# MCU025B_XDS110_MCU.net
KiCad netlist of a schematic drawn in Altium Designer
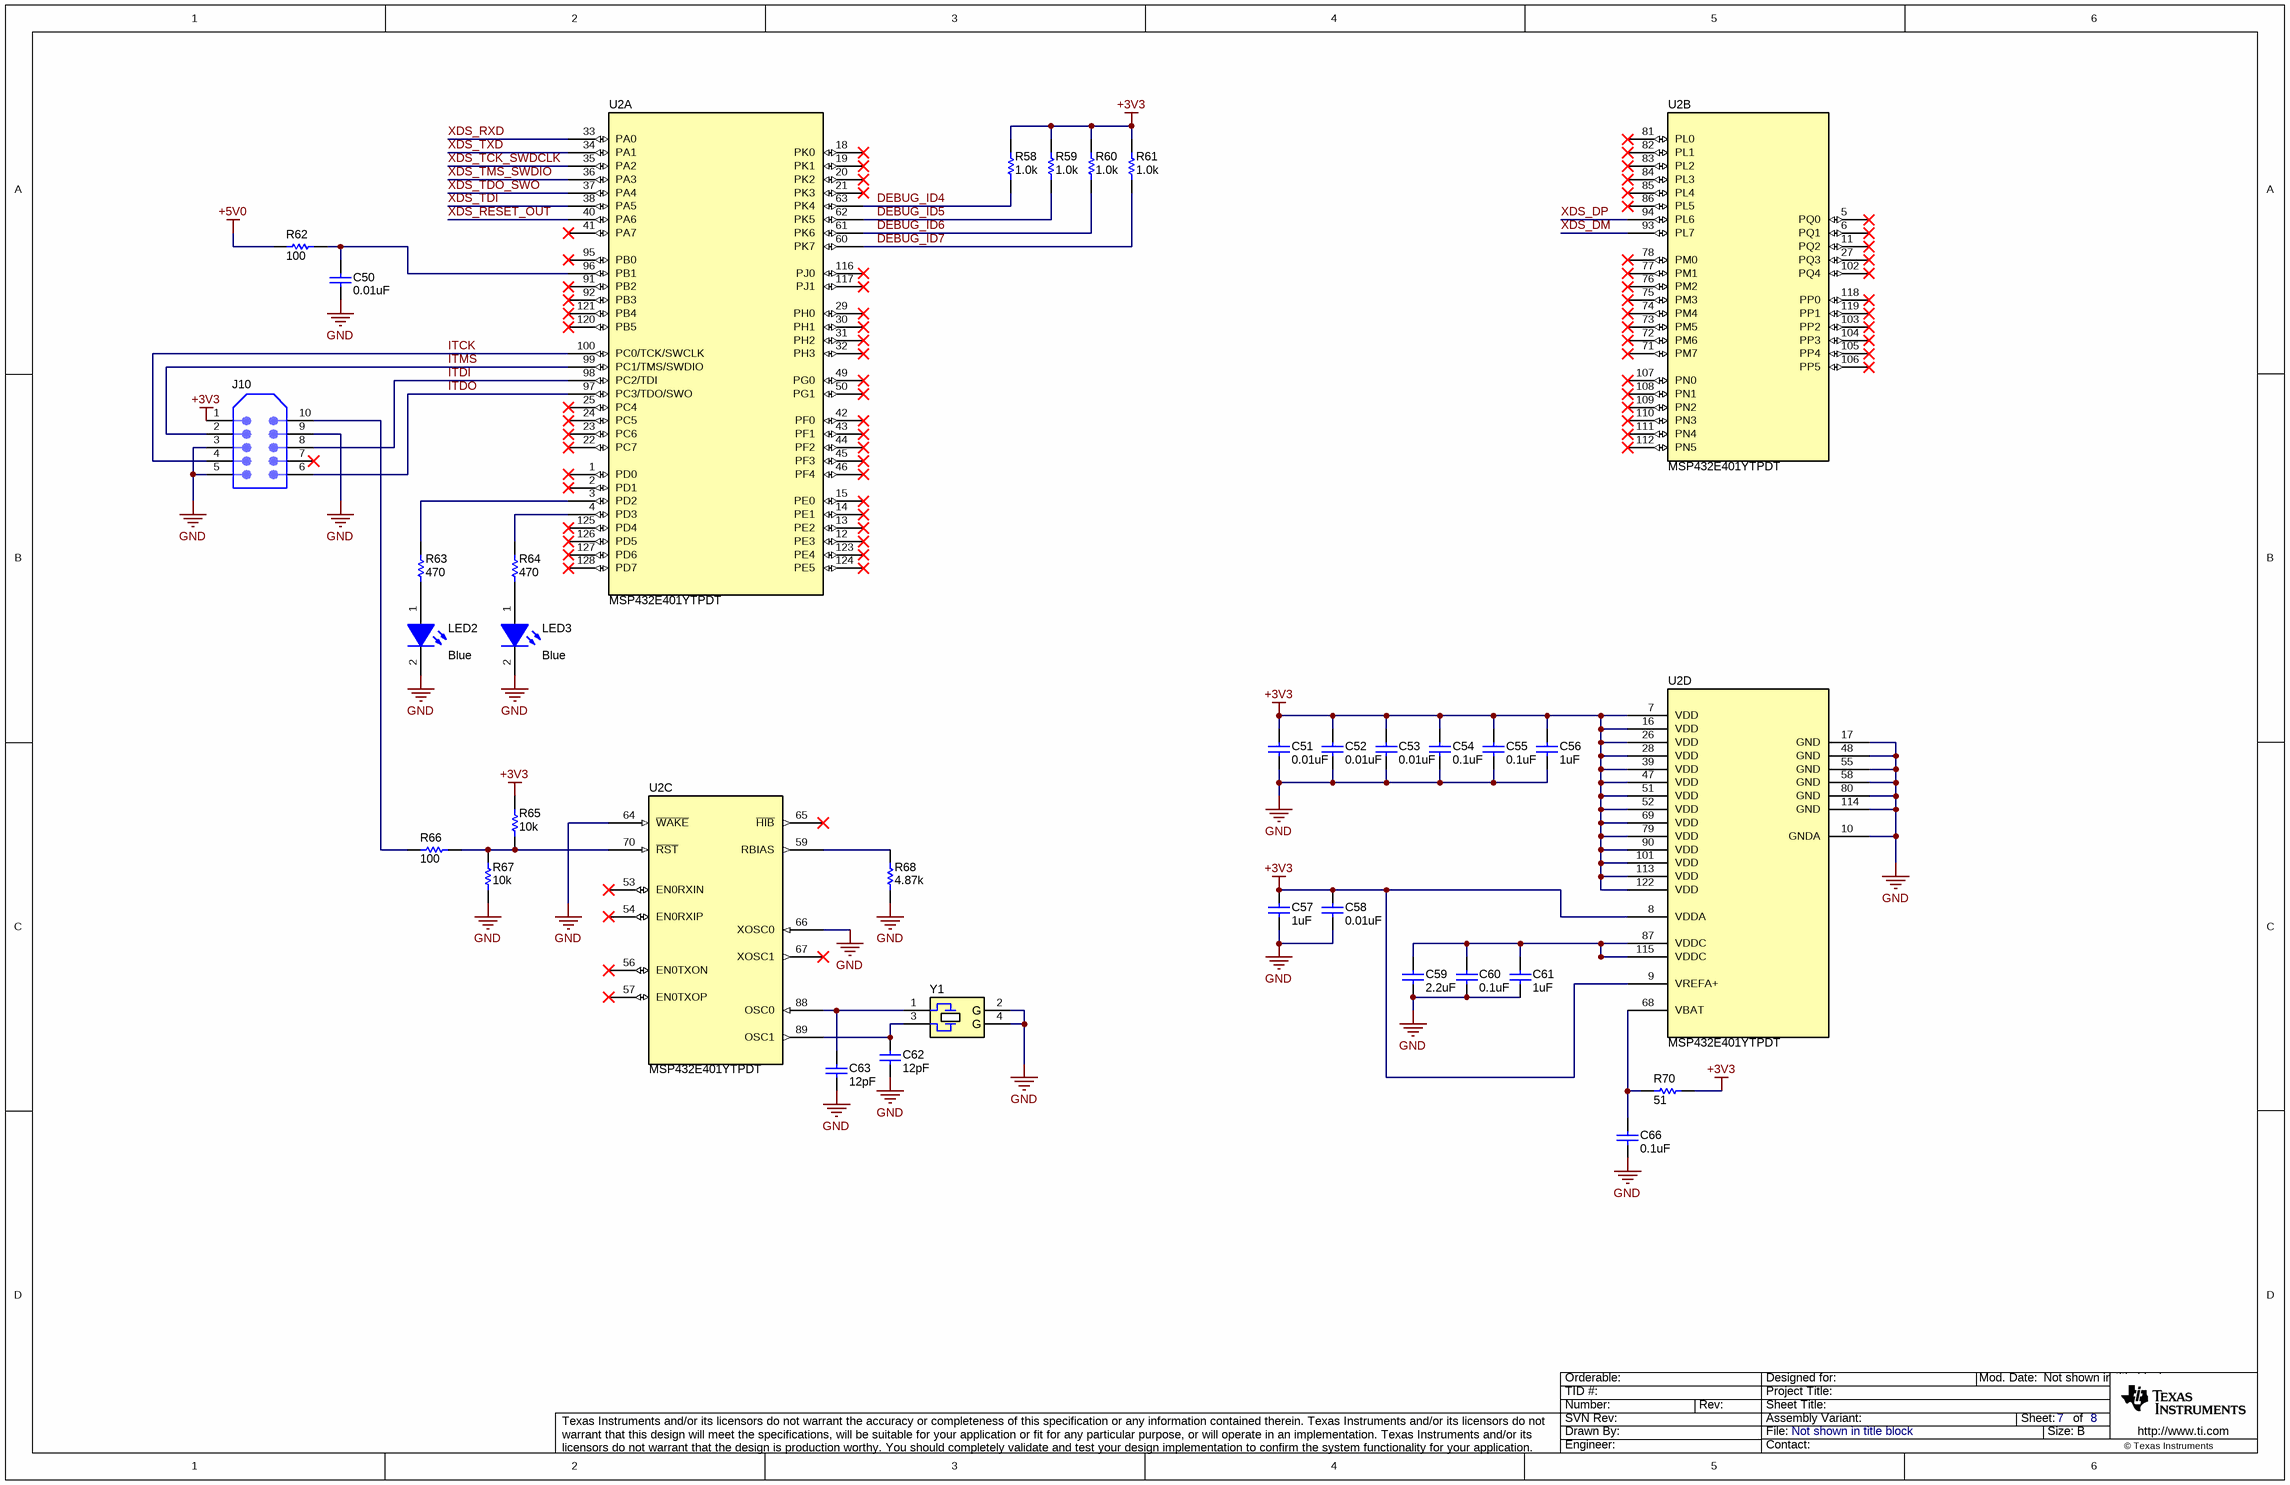
[diagram p0: MCU025B_XDS110_MCU.SchDoc]

(export (version "E")
  (design (tool "Eeschema 10.0.6"))
  (components
    (comp (ref "C50")
      (value "GRM155R71E103KA01D")
      (footprint "0402")
      (description "CAP, CERM, 0.01 uF, 25 V, +/- 10%, X7R, 0402")
      (fields
        (field (name "VALUEDISPLAYED") "0.01uF")
        (field (name "MANUFACTURER") "MuRata")
        (field (name "PUBLISHER") "Texas Instruments")
      )
      (libsource (lib "Altium Vault - TI") (part "Capacitor"))
    )
    (comp (ref "C51")
      (value "GRM155R71E103KA01D")
      (footprint "0402")
      (description "CAP, CERM, 0.01 uF, 25 V, +/- 10%, X7R, 0402")
      (fields
        (field (name "VALUEDISPLAYED") "0.01uF")
        (field (name "MANUFACTURER") "MuRata")
        (field (name "PUBLISHER") "Texas Instruments")
      )
      (libsource (lib "Altium Vault - TI") (part "Capacitor"))
    )
    (comp (ref "C52")
      (value "GRM155R71E103KA01D")
      (footprint "0402")
      (description "CAP, CERM, 0.01 uF, 25 V, +/- 10%, X7R, 0402")
      (fields
        (field (name "VALUEDISPLAYED") "0.01uF")
        (field (name "MANUFACTURER") "MuRata")
        (field (name "PUBLISHER") "Texas Instruments")
      )
      (libsource (lib "Altium Vault - TI") (part "Capacitor"))
    )
    (comp (ref "C53")
      (value "GRM155R71E103KA01D")
      (footprint "0402")
      (description "CAP, CERM, 0.01 uF, 25 V, +/- 10%, X7R, 0402")
      (fields
        (field (name "VALUEDISPLAYED") "0.01uF")
        (field (name "MANUFACTURER") "MuRata")
        (field (name "PUBLISHER") "Texas Instruments")
      )
      (libsource (lib "Altium Vault - TI") (part "Capacitor"))
    )
    (comp (ref "C54")
      (value "GRM155R70J104KA01D")
      (footprint "0402")
      (description "CAP, CERM, 0.1 uF, 6.3 V, +/- 10%, X7R, 0402")
      (fields
        (field (name "VALUEDISPLAYED") "0.1uF")
        (field (name "MANUFACTURER") "MuRata")
        (field (name "PUBLISHER") "Texas Instruments")
      )
      (libsource (lib "Altium Vault - TI") (part "Capacitor"))
    )
    (comp (ref "C55")
      (value "GRM155R70J104KA01D")
      (footprint "0402")
      (description "CAP, CERM, 0.1 uF, 6.3 V, +/- 10%, X7R, 0402")
      (fields
        (field (name "VALUEDISPLAYED") "0.1uF")
        (field (name "MANUFACTURER") "MuRata")
        (field (name "PUBLISHER") "Texas Instruments")
      )
      (libsource (lib "Altium Vault - TI") (part "Capacitor"))
    )
    (comp (ref "C56")
      (value "GRM155R61A105KE15D")
      (footprint "0402")
      (description "CAP, CERM, 1 uF, 10 V, +/- 10%, X5R, 0402")
      (fields
        (field (name "VALUEDISPLAYED") "1uF")
        (field (name "MANUFACTURER") "MuRata")
        (field (name "PUBLISHER") "Texas Instruments")
      )
      (libsource (lib "Altium Vault - TI") (part "Capacitor"))
    )
    (comp (ref "C57")
      (value "GRM155R61A105KE15D")
      (footprint "0402")
      (description "CAP, CERM, 1 uF, 10 V, +/- 10%, X5R, 0402")
      (fields
        (field (name "VALUEDISPLAYED") "1uF")
        (field (name "MANUFACTURER") "MuRata")
        (field (name "PUBLISHER") "Texas Instruments")
      )
      (libsource (lib "Altium Vault - TI") (part "Capacitor"))
    )
    (comp (ref "C58")
      (value "GRM155R71E103KA01D")
      (footprint "0402")
      (description "CAP, CERM, 0.01 uF, 25 V, +/- 10%, X7R, 0402")
      (fields
        (field (name "VALUEDISPLAYED") "0.01uF")
        (field (name "MANUFACTURER") "MuRata")
        (field (name "PUBLISHER") "Texas Instruments")
      )
      (libsource (lib "Altium Vault - TI") (part "Capacitor"))
    )
    (comp (ref "C59")
      (value "GRM155R60J225KE95D")
      (footprint "0402")
      (description "CAP, CERM, 2.2 uF, 6.3 V, +/- 10%, X5R, 0402")
      (fields
        (field (name "VALUEDISPLAYED") "2.2uF")
        (field (name "MANUFACTURER") "MuRata")
        (field (name "PUBLISHER") "Texas Instruments")
      )
      (libsource (lib "Altium Vault - TI") (part "Capacitor"))
    )
    (comp (ref "C60")
      (value "GRM155R70J104KA01D")
      (footprint "0402")
      (description "CAP, CERM, 0.1 uF, 6.3 V, +/- 10%, X7R, 0402")
      (fields
        (field (name "VALUEDISPLAYED") "0.1uF")
        (field (name "MANUFACTURER") "MuRata")
        (field (name "PUBLISHER") "Texas Instruments")
      )
      (libsource (lib "Altium Vault - TI") (part "Capacitor"))
    )
    (comp (ref "C61")
      (value "GRM155R61A105KE15D")
      (footprint "0402")
      (description "CAP, CERM, 1 uF, 10 V, +/- 10%, X5R, 0402")
      (fields
        (field (name "VALUEDISPLAYED") "1uF")
        (field (name "MANUFACTURER") "MuRata")
        (field (name "PUBLISHER") "Texas Instruments")
      )
      (libsource (lib "Altium Vault - TI") (part "Capacitor"))
    )
    (comp (ref "C62")
      (value "GRM1555C1H120JA01D")
      (footprint "0402")
      (description "CAP, CERM, 12 pF, 50 V, +/- 5%, C0G/NP0, 0402")
      (fields
        (field (name "VALUEDISPLAYED") "12pF")
        (field (name "MANUFACTURER") "MuRata")
        (field (name "PUBLISHER") "Texas Instruments")
      )
      (libsource (lib "Altium Vault - TI") (part "Capacitor"))
    )
    (comp (ref "C63")
      (value "GRM1555C1H120JA01D")
      (footprint "0402")
      (description "CAP, CERM, 12 pF, 50 V, +/- 5%, C0G/NP0, 0402")
      (fields
        (field (name "VALUEDISPLAYED") "12pF")
        (field (name "MANUFACTURER") "MuRata")
        (field (name "PUBLISHER") "Texas Instruments")
      )
      (libsource (lib "Altium Vault - TI") (part "Capacitor"))
    )
    (comp (ref "C66")
      (value "GRM155R70J104KA01D")
      (footprint "0402")
      (description "CAP, CERM, 0.1 uF, 6.3 V, +/- 10%, X7R, 0402")
      (fields
        (field (name "VALUEDISPLAYED") "0.1uF")
        (field (name "MANUFACTURER") "MuRata")
        (field (name "PUBLISHER") "Texas Instruments")
      )
      (libsource (lib "Altium Vault - TI") (part "Capacitor"))
    )
    (comp (ref "J10")
      (value "TC2050-IDC-NL-FP")
      (footprint "Tag_TC2050-NL")
      (description "Footprint for Tag-Connect TC2050 No-Legs cables")
      (fields (field (name "MANUFACTURER") "Tag-Connect") (field (name "PUBLISHER") "Texas Instruments"))
      (libsource (lib "Altium Vault - TI") (part "CMP-0075101-1"))
    )
    (comp (ref "LED2")
      (value "Blue")
      (footprint "LTST-C170TBKT_Blue")
      (description "LED, Blue, SMD")
      (fields
        (field (name "PARTNUMBER") "LTST-C170TBKT")
        (field (name "MANUFACTURER") "Lite-On")
        (field (name "PUBLISHER") "Texas Instruments")
      )
      (libsource (lib "Altium Vault - TI") (part "CMP-0002889-1"))
    )
    (comp (ref "LED3")
      (value "Blue")
      (footprint "LTST-C170TBKT_Blue")
      (description "LED, Blue, SMD")
      (fields
        (field (name "PARTNUMBER") "LTST-C170TBKT")
        (field (name "MANUFACTURER") "Lite-On")
        (field (name "PUBLISHER") "Texas Instruments")
      )
      (libsource (lib "Altium Vault - TI") (part "CMP-0002889-1"))
    )
    (comp (ref "R58")
      (value "CRCW04021K00JNED")
      (footprint "0402")
      (description "RES, 1.0 k, 5%, 0.063 W, AEC-Q200 Grade 0, 0402")
      (fields (field (name "MANUFACTURER") "Vishay-Dale") (field (name "VALUEDISPLAYED") "1.0k"))
      (libsource (lib "Altium Vault - TI") (part "Resistor"))
    )
    (comp (ref "R59")
      (value "CRCW04021K00JNED")
      (footprint "0402")
      (description "RES, 1.0 k, 5%, 0.063 W, AEC-Q200 Grade 0, 0402")
      (fields (field (name "MANUFACTURER") "Vishay-Dale") (field (name "VALUEDISPLAYED") "1.0k"))
      (libsource (lib "Altium Vault - TI") (part "Resistor"))
    )
    (comp (ref "R60")
      (value "CRCW04021K00JNED")
      (footprint "0402")
      (description "RES, 1.0 k, 5%, 0.063 W, AEC-Q200 Grade 0, 0402")
      (fields (field (name "MANUFACTURER") "Vishay-Dale") (field (name "VALUEDISPLAYED") "1.0k"))
      (libsource (lib "Altium Vault - TI") (part "Resistor"))
    )
    (comp (ref "R61")
      (value "CRCW04021K00JNED")
      (footprint "0402")
      (description "RES, 1.0 k, 5%, 0.063 W, AEC-Q200 Grade 0, 0402")
      (fields (field (name "MANUFACTURER") "Vishay-Dale") (field (name "VALUEDISPLAYED") "1.0k"))
      (libsource (lib "Altium Vault - TI") (part "Resistor"))
    )
    (comp (ref "R62")
      (value "CRCW0402100RJNED")
      (footprint "0402")
      (description "RES, 100, 5%, 0.063 W, AEC-Q200 Grade 0, 0402")
      (fields (field (name "VALUEDISPLAYED") "100") (field (name "MANUFACTURER") "Vishay-Dale"))
      (libsource (lib "Altium Vault - TI") (part "Resistor"))
    )
    (comp (ref "R63")
      (value "ERJ-2RKF4700X")
      (footprint "0402")
      (description "RES, 470, 1%, 0.1 W, AEC-Q200 Grade 0, 0402")
      (fields
        (field (name "VALUEDISPLAYED") "470")
        (field (name "MANUFACTURER") "Panasonic")
        (field (name "PUBLISHER") "Texas Instruments")
      )
      (libsource (lib "Altium Vault - TI") (part "Resistor"))
    )
    (comp (ref "R64")
      (value "ERJ-2RKF4700X")
      (footprint "0402")
      (description "RES, 470, 1%, 0.1 W, AEC-Q200 Grade 0, 0402")
      (fields
        (field (name "VALUEDISPLAYED") "470")
        (field (name "MANUFACTURER") "Panasonic")
        (field (name "PUBLISHER") "Texas Instruments")
      )
      (libsource (lib "Altium Vault - TI") (part "Resistor"))
    )
    (comp (ref "R65")
      (value "CRCW040210K0JNED")
      (footprint "0402")
      (description "RES, 10 k, 5%, 0.063 W, AEC-Q200 Grade 0, 0402")
      (fields (field (name "VALUEDISPLAYED") "10k") (field (name "MANUFACTURER") "Vishay-Dale"))
      (libsource (lib "Altium Vault - TI") (part "Resistor"))
    )
    (comp (ref "R66")
      (value "CRCW0402100RJNED")
      (footprint "0402")
      (description "RES, 100, 5%, 0.063 W, AEC-Q200 Grade 0, 0402")
      (fields (field (name "VALUEDISPLAYED") "100") (field (name "MANUFACTURER") "Vishay-Dale"))
      (libsource (lib "Altium Vault - TI") (part "Resistor"))
    )
    (comp (ref "R67")
      (value "CRCW040210K0JNED")
      (footprint "0402")
      (description "RES, 10 k, 5%, 0.063 W, AEC-Q200 Grade 0, 0402")
      (fields (field (name "VALUEDISPLAYED") "10k") (field (name "MANUFACTURER") "Vishay-Dale"))
      (libsource (lib "Altium Vault - TI") (part "Resistor"))
    )
    (comp (ref "R68")
      (value "CRCW04024K87FKED")
      (footprint "0402")
      (description "RES, 4.87 k, 1%, 0.063 W, AEC-Q200 Grade 0, 0402")
      (fields (field (name "VALUEDISPLAYED") "4.87k") (field (name "MANUFACTURER") "Vishay-Dale"))
      (libsource (lib "Altium Vault - TI") (part "Resistor"))
    )
    (comp (ref "R70")
      (value "CRCW040251R0JNED")
      (footprint "0402")
      (description "RES, 51, 5%, 0.063 W, AEC-Q200 Grade 0, 0402")
      (fields (field (name "VALUEDISPLAYED") "51") (field (name "MANUFACTURER") "Vishay-Dale"))
      (libsource (lib "Altium Vault - TI") (part "Resistor"))
    )
    (comp (ref "U2")
      (value "MSP432E401YTPDT")
      (footprint "PDT0128A")
      (description "MSP432E401YTPDT, PDT0128A (TQFP-128)")
      (fields
        (field (name "ALTERNATE PARTNUMBER") "MSP432E401YTPDTR")
        (field (name "MANUFACTURER") "Texas Instruments")
        (field (name "PARTNUMBER") "MSP432E401YTPDT")
      )
      (libsource (lib "Altium Vault - TI") (part "MSP432E401YTPDT"))
    )
    (comp (ref "Y1")
      (value "NX3225GA-16.000M-STD-CRG-1")
      (footprint "NDK_NX3225GA")
      (description "Crystal, 16 MHz, 8pF, SMD")
      (fields (field (name "MANUFACTURER") "NDK"))
      (libsource (lib "Altium Vault - TI") (part "XTAL_4P_13_G24"))
    )
  )
  (nets
    (net (code "1") (name "+3V3") (class "Default")
      (node (ref "C51") (pin "1") (pinfunction "1_1") (pintype "passive"))
      (node (ref "C52") (pin "1") (pinfunction "1_1") (pintype "passive"))
      (node (ref "C53") (pin "1") (pinfunction "1_1") (pintype "passive"))
      (node (ref "C54") (pin "1") (pinfunction "1_1") (pintype "passive"))
      (node (ref "C55") (pin "1") (pinfunction "1_1") (pintype "passive"))
      (node (ref "C56") (pin "1") (pinfunction "1_1") (pintype "passive"))
      (node (ref "C57") (pin "1") (pinfunction "1_1") (pintype "passive"))
      (node (ref "C58") (pin "1") (pinfunction "1_1") (pintype "passive"))
      (node (ref "J10") (pin "1") (pinfunction "1_1") (pintype "passive"))
      (node (ref "R58") (pin "2") (pinfunction "2_2") (pintype "passive"))
      (node (ref "R59") (pin "2") (pinfunction "2_2") (pintype "passive"))
      (node (ref "R60") (pin "2") (pinfunction "2_2") (pintype "passive"))
      (node (ref "R61") (pin "2") (pinfunction "2_2") (pintype "passive"))
      (node (ref "R65") (pin "2") (pinfunction "2_2") (pintype "passive"))
      (node (ref "R70") (pin "2") (pinfunction "2_2") (pintype "passive"))
      (node (ref "U2") (pin "101") (pinfunction "VDD_101") (pintype "power_in"))
      (node (ref "U2") (pin "113") (pinfunction "VDD_113") (pintype "power_in"))
      (node (ref "U2") (pin "122") (pinfunction "VDD_122") (pintype "power_in"))
      (node (ref "U2") (pin "16") (pinfunction "VDD_16") (pintype "power_in"))
      (node (ref "U2") (pin "26") (pinfunction "VDD_26") (pintype "power_in"))
      (node (ref "U2") (pin "28") (pinfunction "VDD_28") (pintype "power_in"))
      (node (ref "U2") (pin "39") (pinfunction "VDD_39") (pintype "power_in"))
      (node (ref "U2") (pin "47") (pinfunction "VDD_47") (pintype "power_in"))
      (node (ref "U2") (pin "51") (pinfunction "VDD_51") (pintype "power_in"))
      (node (ref "U2") (pin "52") (pinfunction "VDD_52") (pintype "power_in"))
      (node (ref "U2") (pin "69") (pinfunction "VDD_69") (pintype "power_in"))
      (node (ref "U2") (pin "7") (pinfunction "VDD_7") (pintype "power_in"))
      (node (ref "U2") (pin "79") (pinfunction "VDD_79") (pintype "power_in"))
      (node (ref "U2") (pin "8") (pinfunction "VDDA_8") (pintype "power_in"))
      (node (ref "U2") (pin "9") (pinfunction "VREFA+_9") (pintype "power_in"))
      (node (ref "U2") (pin "90") (pinfunction "VDD_90") (pintype "power_in"))
    )
    (net (code "2") (name "+5V0") (class "Default")
      (node (ref "R62") (pin "1") (pinfunction "1_1") (pintype "passive"))
    )
    (net (code "3") (name "/DEBUG_ID4") (class "Default")
      (node (ref "R58") (pin "1") (pinfunction "1_1") (pintype "passive"))
      (node (ref "U2") (pin "63") (pinfunction "PK4_63") (pintype "bidirectional"))
    )
    (net (code "4") (name "/DEBUG_ID5") (class "Default")
      (node (ref "R59") (pin "1") (pinfunction "1_1") (pintype "passive"))
      (node (ref "U2") (pin "62") (pinfunction "PK5_62") (pintype "bidirectional"))
    )
    (net (code "5") (name "/DEBUG_ID6") (class "Default")
      (node (ref "R60") (pin "1") (pinfunction "1_1") (pintype "passive"))
      (node (ref "U2") (pin "61") (pinfunction "PK6_61") (pintype "bidirectional"))
    )
    (net (code "6") (name "/DEBUG_ID7") (class "Default")
      (node (ref "R61") (pin "1") (pinfunction "1_1") (pintype "passive"))
      (node (ref "U2") (pin "60") (pinfunction "PK7_60") (pintype "bidirectional"))
    )
    (net (code "7") (name "/ITCK") (class "Default")
      (node (ref "J10") (pin "4") (pinfunction "4_4") (pintype "passive"))
      (node (ref "U2") (pin "100") (pinfunction "PC0/TCK/SWCLK_100") (pintype "bidirectional"))
    )
    (net (code "8") (name "/ITDI") (class "Default")
      (node (ref "J10") (pin "8") (pinfunction "8_8") (pintype "passive"))
      (node (ref "U2") (pin "98") (pinfunction "PC2/TDI_98") (pintype "bidirectional"))
    )
    (net (code "9") (name "/ITDO") (class "Default")
      (node (ref "J10") (pin "6") (pinfunction "6_6") (pintype "passive"))
      (node (ref "U2") (pin "97") (pinfunction "PC3/TDO/SWO_97") (pintype "bidirectional"))
    )
    (net (code "10") (name "/ITMS") (class "Default")
      (node (ref "J10") (pin "2") (pinfunction "2_2") (pintype "passive"))
      (node (ref "U2") (pin "99") (pinfunction "PC1/TMS/SWDIO_99") (pintype "bidirectional"))
    )
    (net (code "11") (name "/XDS_DM") (class "Default")
      (node (ref "U2") (pin "93") (pinfunction "PL7_93") (pintype "bidirectional"))
    )
    (net (code "12") (name "/XDS_DP") (class "Default")
      (node (ref "U2") (pin "94") (pinfunction "PL6_94") (pintype "bidirectional"))
    )
    (net (code "13") (name "/XDS_RESET_OUT") (class "Default")
      (node (ref "U2") (pin "40") (pinfunction "PA6_40") (pintype "bidirectional"))
    )
    (net (code "14") (name "/XDS_RXD") (class "Default")
      (node (ref "U2") (pin "33") (pinfunction "PA0_33") (pintype "bidirectional"))
    )
    (net (code "15") (name "/XDS_TCK_SWDCLK") (class "Default")
      (node (ref "U2") (pin "35") (pinfunction "PA2_35") (pintype "bidirectional"))
    )
    (net (code "16") (name "/XDS_TDI") (class "Default")
      (node (ref "U2") (pin "38") (pinfunction "PA5_38") (pintype "bidirectional"))
    )
    (net (code "17") (name "/XDS_TDO_SWO") (class "Default")
      (node (ref "U2") (pin "37") (pinfunction "PA4_37") (pintype "bidirectional"))
    )
    (net (code "18") (name "/XDS_TMS_SWDIO") (class "Default")
      (node (ref "U2") (pin "36") (pinfunction "PA3_36") (pintype "bidirectional"))
    )
    (net (code "19") (name "/XDS_TXD") (class "Default")
      (node (ref "U2") (pin "34") (pinfunction "PA1_34") (pintype "bidirectional"))
    )
    (net (code "20") (name "GND") (class "Default")
      (node (ref "C50") (pin "2") (pinfunction "2_2") (pintype "passive"))
      (node (ref "C51") (pin "2") (pinfunction "2_2") (pintype "passive"))
      (node (ref "C52") (pin "2") (pinfunction "2_2") (pintype "passive"))
      (node (ref "C53") (pin "2") (pinfunction "2_2") (pintype "passive"))
      (node (ref "C54") (pin "2") (pinfunction "2_2") (pintype "passive"))
      (node (ref "C55") (pin "2") (pinfunction "2_2") (pintype "passive"))
      (node (ref "C56") (pin "2") (pinfunction "2_2") (pintype "passive"))
      (node (ref "C57") (pin "2") (pinfunction "2_2") (pintype "passive"))
      (node (ref "C58") (pin "2") (pinfunction "2_2") (pintype "passive"))
      (node (ref "C59") (pin "2") (pinfunction "2_2") (pintype "passive"))
      (node (ref "C60") (pin "2") (pinfunction "2_2") (pintype "passive"))
      (node (ref "C61") (pin "2") (pinfunction "2_2") (pintype "passive"))
      (node (ref "C62") (pin "2") (pinfunction "2_2") (pintype "passive"))
      (node (ref "C63") (pin "2") (pinfunction "2_2") (pintype "passive"))
      (node (ref "C66") (pin "2") (pinfunction "2_2") (pintype "passive"))
      (node (ref "J10") (pin "3") (pinfunction "3_3") (pintype "passive"))
      (node (ref "J10") (pin "5") (pinfunction "5_5") (pintype "passive"))
      (node (ref "J10") (pin "9") (pinfunction "9_9") (pintype "passive"))
      (node (ref "LED2") (pin "2") (pinfunction "K_2") (pintype "passive"))
      (node (ref "LED3") (pin "2") (pinfunction "K_2") (pintype "passive"))
      (node (ref "R67") (pin "1") (pinfunction "1_1") (pintype "passive"))
      (node (ref "R68") (pin "1") (pinfunction "1_1") (pintype "passive"))
      (node (ref "U2") (pin "10") (pinfunction "GNDA_10") (pintype "power_in"))
      (node (ref "U2") (pin "114") (pinfunction "GND_114") (pintype "power_in"))
      (node (ref "U2") (pin "17") (pinfunction "GND_17") (pintype "power_in"))
      (node (ref "U2") (pin "48") (pinfunction "GND_48") (pintype "power_in"))
      (node (ref "U2") (pin "55") (pinfunction "GND_55") (pintype "power_in"))
      (node (ref "U2") (pin "58") (pinfunction "GND_58") (pintype "power_in"))
      (node (ref "U2") (pin "64") (pinfunction "WAKE_64") (pintype "input"))
      (node (ref "U2") (pin "66") (pinfunction "XOSC0_66") (pintype "input"))
      (node (ref "U2") (pin "80") (pinfunction "GND_80") (pintype "power_in"))
      (node (ref "Y1") (pin "2") (pinfunction "GND_2") (pintype "power_in"))
      (node (ref "Y1") (pin "4") (pinfunction "GND_4") (pintype "power_in"))
    )
    (net (code "21") (name "Net-(C59-Pad1)") (class "Default")
      (node (ref "C59") (pin "1") (pinfunction "1_1") (pintype "passive"))
      (node (ref "C60") (pin "1") (pinfunction "1_1") (pintype "passive"))
      (node (ref "C61") (pin "1") (pinfunction "1_1") (pintype "passive"))
      (node (ref "U2") (pin "115") (pinfunction "VDDC_115") (pintype "power_in"))
      (node (ref "U2") (pin "87") (pinfunction "VDDC_87") (pintype "power_in"))
    )
    (net (code "22") (name "Net-(J10-Pad10)") (class "Default")
      (node (ref "J10") (pin "10") (pinfunction "10_10") (pintype "passive"))
      (node (ref "R66") (pin "1") (pinfunction "1_1") (pintype "passive"))
    )
    (net (code "23") (name "Net-(LED2-A)") (class "Default")
      (node (ref "LED2") (pin "1") (pinfunction "A_1") (pintype "passive"))
      (node (ref "R63") (pin "1") (pinfunction "1_1") (pintype "passive"))
    )
    (net (code "24") (name "Net-(LED3-A)") (class "Default")
      (node (ref "LED3") (pin "1") (pinfunction "A_1") (pintype "passive"))
      (node (ref "R64") (pin "1") (pinfunction "1_1") (pintype "passive"))
    )
    (net (code "25") (name "Net-(U2A-PB1)") (class "Default")
      (node (ref "C50") (pin "1") (pinfunction "1_1") (pintype "passive"))
      (node (ref "R62") (pin "2") (pinfunction "2_2") (pintype "passive"))
      (node (ref "U2") (pin "96") (pinfunction "PB1_96") (pintype "bidirectional"))
    )
    (net (code "26") (name "Net-(U2A-PD2)") (class "Default")
      (node (ref "R63") (pin "2") (pinfunction "2_2") (pintype "passive"))
      (node (ref "U2") (pin "3") (pinfunction "PD2_3") (pintype "bidirectional"))
    )
    (net (code "27") (name "Net-(U2A-PD3)") (class "Default")
      (node (ref "R64") (pin "2") (pinfunction "2_2") (pintype "passive"))
      (node (ref "U2") (pin "4") (pinfunction "PD3_4") (pintype "bidirectional"))
    )
    (net (code "28") (name "Net-(U2C-OSC0)") (class "Default")
      (node (ref "C63") (pin "1") (pinfunction "1_1") (pintype "passive"))
      (node (ref "U2") (pin "88") (pinfunction "OSC0_88") (pintype "input"))
      (node (ref "Y1") (pin "1") (pinfunction "1_1") (pintype "passive"))
    )
    (net (code "29") (name "Net-(U2C-OSC1)") (class "Default")
      (node (ref "C62") (pin "1") (pinfunction "1_1") (pintype "passive"))
      (node (ref "U2") (pin "89") (pinfunction "OSC1_89") (pintype "output"))
      (node (ref "Y1") (pin "3") (pinfunction "3_3") (pintype "passive"))
    )
    (net (code "30") (name "Net-(U2C-RBIAS)") (class "Default")
      (node (ref "R68") (pin "2") (pinfunction "2_2") (pintype "passive"))
      (node (ref "U2") (pin "59") (pinfunction "RBIAS_59") (pintype "output"))
    )
    (net (code "31") (name "Net-(U2C-RST)") (class "Default")
      (node (ref "R65") (pin "1") (pinfunction "1_1") (pintype "passive"))
      (node (ref "R66") (pin "2") (pinfunction "2_2") (pintype "passive"))
      (node (ref "R67") (pin "2") (pinfunction "2_2") (pintype "passive"))
      (node (ref "U2") (pin "70") (pinfunction "RST_70") (pintype "input"))
    )
    (net (code "32") (name "Net-(U2D-VBAT)") (class "Default")
      (node (ref "C66") (pin "1") (pinfunction "1_1") (pintype "passive"))
      (node (ref "R70") (pin "1") (pinfunction "1_1") (pintype "passive"))
      (node (ref "U2") (pin "68") (pinfunction "VBAT_68") (pintype "power_in"))
    )
    (net (code "33") (name "unconnected-(J10-Pad7)") (class "Default")
      (node (ref "J10") (pin "7") (pinfunction "7_7") (pintype "passive+no_connect"))
    )
    (net (code "34") (name "unconnected-(U2A-PA7-Pad41)") (class "Default")
      (node (ref "U2") (pin "41") (pinfunction "PA7_41") (pintype "bidirectional+no_connect"))
    )
    (net (code "35") (name "unconnected-(U2A-PB0-Pad95)") (class "Default")
      (node (ref "U2") (pin "95") (pinfunction "PB0_95") (pintype "bidirectional+no_connect"))
    )
    (net (code "36") (name "unconnected-(U2A-PB2-Pad91)") (class "Default")
      (node (ref "U2") (pin "91") (pinfunction "PB2_91") (pintype "bidirectional+no_connect"))
    )
    (net (code "37") (name "unconnected-(U2A-PB3-Pad92)") (class "Default")
      (node (ref "U2") (pin "92") (pinfunction "PB3_92") (pintype "bidirectional+no_connect"))
    )
    (net (code "38") (name "unconnected-(U2A-PB4-Pad121)") (class "Default")
      (node (ref "U2") (pin "121") (pinfunction "PB4_121") (pintype "bidirectional+no_connect"))
    )
    (net (code "39") (name "unconnected-(U2A-PB5-Pad120)") (class "Default")
      (node (ref "U2") (pin "120") (pinfunction "PB5_120") (pintype "bidirectional+no_connect"))
    )
    (net (code "40") (name "unconnected-(U2A-PC4-Pad25)") (class "Default")
      (node (ref "U2") (pin "25") (pinfunction "PC4_25") (pintype "bidirectional+no_connect"))
    )
    (net (code "41") (name "unconnected-(U2A-PC5-Pad24)") (class "Default")
      (node (ref "U2") (pin "24") (pinfunction "PC5_24") (pintype "bidirectional+no_connect"))
    )
    (net (code "42") (name "unconnected-(U2A-PC6-Pad23)") (class "Default")
      (node (ref "U2") (pin "23") (pinfunction "PC6_23") (pintype "bidirectional+no_connect"))
    )
    (net (code "43") (name "unconnected-(U2A-PC7-Pad22)") (class "Default")
      (node (ref "U2") (pin "22") (pinfunction "PC7_22") (pintype "bidirectional+no_connect"))
    )
    (net (code "44") (name "unconnected-(U2A-PD0-Pad1)") (class "Default")
      (node (ref "U2") (pin "1") (pinfunction "PD0_1") (pintype "bidirectional+no_connect"))
    )
    (net (code "45") (name "unconnected-(U2A-PD1-Pad2)") (class "Default")
      (node (ref "U2") (pin "2") (pinfunction "PD1_2") (pintype "bidirectional+no_connect"))
    )
    (net (code "46") (name "unconnected-(U2A-PD4-Pad125)") (class "Default")
      (node (ref "U2") (pin "125") (pinfunction "PD4_125") (pintype "bidirectional+no_connect"))
    )
    (net (code "47") (name "unconnected-(U2A-PD5-Pad126)") (class "Default")
      (node (ref "U2") (pin "126") (pinfunction "PD5_126") (pintype "bidirectional+no_connect"))
    )
    (net (code "48") (name "unconnected-(U2A-PD6-Pad127)") (class "Default")
      (node (ref "U2") (pin "127") (pinfunction "PD6_127") (pintype "bidirectional+no_connect"))
    )
    (net (code "49") (name "unconnected-(U2A-PD7-Pad128)") (class "Default")
      (node (ref "U2") (pin "128") (pinfunction "PD7_128") (pintype "bidirectional+no_connect"))
    )
    (net (code "50") (name "unconnected-(U2A-PE0-Pad15)") (class "Default")
      (node (ref "U2") (pin "15") (pinfunction "PE0_15") (pintype "bidirectional+no_connect"))
    )
    (net (code "51") (name "unconnected-(U2A-PE1-Pad14)") (class "Default")
      (node (ref "U2") (pin "14") (pinfunction "PE1_14") (pintype "bidirectional+no_connect"))
    )
    (net (code "52") (name "unconnected-(U2A-PE2-Pad13)") (class "Default")
      (node (ref "U2") (pin "13") (pinfunction "PE2_13") (pintype "bidirectional+no_connect"))
    )
    (net (code "53") (name "unconnected-(U2A-PE3-Pad12)") (class "Default")
      (node (ref "U2") (pin "12") (pinfunction "PE3_12") (pintype "bidirectional+no_connect"))
    )
    (net (code "54") (name "unconnected-(U2A-PE4-Pad123)") (class "Default")
      (node (ref "U2") (pin "123") (pinfunction "PE4_123") (pintype "bidirectional+no_connect"))
    )
    (net (code "55") (name "unconnected-(U2A-PE5-Pad124)") (class "Default")
      (node (ref "U2") (pin "124") (pinfunction "PE5_124") (pintype "bidirectional+no_connect"))
    )
    (net (code "56") (name "unconnected-(U2A-PF0-Pad42)") (class "Default")
      (node (ref "U2") (pin "42") (pinfunction "PF0_42") (pintype "bidirectional+no_connect"))
    )
    (net (code "57") (name "unconnected-(U2A-PF1-Pad43)") (class "Default")
      (node (ref "U2") (pin "43") (pinfunction "PF1_43") (pintype "bidirectional+no_connect"))
    )
    (net (code "58") (name "unconnected-(U2A-PF2-Pad44)") (class "Default")
      (node (ref "U2") (pin "44") (pinfunction "PF2_44") (pintype "bidirectional+no_connect"))
    )
    (net (code "59") (name "unconnected-(U2A-PF3-Pad45)") (class "Default")
      (node (ref "U2") (pin "45") (pinfunction "PF3_45") (pintype "bidirectional+no_connect"))
    )
    (net (code "60") (name "unconnected-(U2A-PF4-Pad46)") (class "Default")
      (node (ref "U2") (pin "46") (pinfunction "PF4_46") (pintype "bidirectional+no_connect"))
    )
    (net (code "61") (name "unconnected-(U2A-PG0-Pad49)") (class "Default")
      (node (ref "U2") (pin "49") (pinfunction "PG0_49") (pintype "bidirectional+no_connect"))
    )
    (net (code "62") (name "unconnected-(U2A-PG1-Pad50)") (class "Default")
      (node (ref "U2") (pin "50") (pinfunction "PG1_50") (pintype "bidirectional+no_connect"))
    )
    (net (code "63") (name "unconnected-(U2A-PH0-Pad29)") (class "Default")
      (node (ref "U2") (pin "29") (pinfunction "PH0_29") (pintype "bidirectional+no_connect"))
    )
    (net (code "64") (name "unconnected-(U2A-PH1-Pad30)") (class "Default")
      (node (ref "U2") (pin "30") (pinfunction "PH1_30") (pintype "bidirectional+no_connect"))
    )
    (net (code "65") (name "unconnected-(U2A-PH2-Pad31)") (class "Default")
      (node (ref "U2") (pin "31") (pinfunction "PH2_31") (pintype "bidirectional+no_connect"))
    )
    (net (code "66") (name "unconnected-(U2A-PH3-Pad32)") (class "Default")
      (node (ref "U2") (pin "32") (pinfunction "PH3_32") (pintype "bidirectional+no_connect"))
    )
    (net (code "67") (name "unconnected-(U2A-PJ0-Pad116)") (class "Default")
      (node (ref "U2") (pin "116") (pinfunction "PJ0_116") (pintype "bidirectional+no_connect"))
    )
    (net (code "68") (name "unconnected-(U2A-PJ1-Pad117)") (class "Default")
      (node (ref "U2") (pin "117") (pinfunction "PJ1_117") (pintype "bidirectional+no_connect"))
    )
    (net (code "69") (name "unconnected-(U2A-PK0-Pad18)") (class "Default")
      (node (ref "U2") (pin "18") (pinfunction "PK0_18") (pintype "bidirectional+no_connect"))
    )
    (net (code "70") (name "unconnected-(U2A-PK1-Pad19)") (class "Default")
      (node (ref "U2") (pin "19") (pinfunction "PK1_19") (pintype "bidirectional+no_connect"))
    )
    (net (code "71") (name "unconnected-(U2A-PK2-Pad20)") (class "Default")
      (node (ref "U2") (pin "20") (pinfunction "PK2_20") (pintype "bidirectional+no_connect"))
    )
    (net (code "72") (name "unconnected-(U2A-PK3-Pad21)") (class "Default")
      (node (ref "U2") (pin "21") (pinfunction "PK3_21") (pintype "bidirectional+no_connect"))
    )
    (net (code "73") (name "unconnected-(U2B-PL0-Pad81)") (class "Default")
      (node (ref "U2") (pin "81") (pinfunction "PL0_81") (pintype "bidirectional+no_connect"))
    )
    (net (code "74") (name "unconnected-(U2B-PL1-Pad82)") (class "Default")
      (node (ref "U2") (pin "82") (pinfunction "PL1_82") (pintype "bidirectional+no_connect"))
    )
    (net (code "75") (name "unconnected-(U2B-PL2-Pad83)") (class "Default")
      (node (ref "U2") (pin "83") (pinfunction "PL2_83") (pintype "bidirectional+no_connect"))
    )
    (net (code "76") (name "unconnected-(U2B-PL3-Pad84)") (class "Default")
      (node (ref "U2") (pin "84") (pinfunction "PL3_84") (pintype "bidirectional+no_connect"))
    )
    (net (code "77") (name "unconnected-(U2B-PL4-Pad85)") (class "Default")
      (node (ref "U2") (pin "85") (pinfunction "PL4_85") (pintype "bidirectional+no_connect"))
    )
    (net (code "78") (name "unconnected-(U2B-PL5-Pad86)") (class "Default")
      (node (ref "U2") (pin "86") (pinfunction "PL5_86") (pintype "bidirectional+no_connect"))
    )
    (net (code "79") (name "unconnected-(U2B-PM0-Pad78)") (class "Default")
      (node (ref "U2") (pin "78") (pinfunction "PM0_78") (pintype "bidirectional+no_connect"))
    )
    (net (code "80") (name "unconnected-(U2B-PM1-Pad77)") (class "Default")
      (node (ref "U2") (pin "77") (pinfunction "PM1_77") (pintype "bidirectional+no_connect"))
    )
    (net (code "81") (name "unconnected-(U2B-PM2-Pad76)") (class "Default")
      (node (ref "U2") (pin "76") (pinfunction "PM2_76") (pintype "bidirectional+no_connect"))
    )
    (net (code "82") (name "unconnected-(U2B-PM3-Pad75)") (class "Default")
      (node (ref "U2") (pin "75") (pinfunction "PM3_75") (pintype "bidirectional+no_connect"))
    )
    (net (code "83") (name "unconnected-(U2B-PM4-Pad74)") (class "Default")
      (node (ref "U2") (pin "74") (pinfunction "PM4_74") (pintype "bidirectional+no_connect"))
    )
    (net (code "84") (name "unconnected-(U2B-PM5-Pad73)") (class "Default")
      (node (ref "U2") (pin "73") (pinfunction "PM5_73") (pintype "bidirectional+no_connect"))
    )
    (net (code "85") (name "unconnected-(U2B-PM6-Pad72)") (class "Default")
      (node (ref "U2") (pin "72") (pinfunction "PM6_72") (pintype "bidirectional+no_connect"))
    )
    (net (code "86") (name "unconnected-(U2B-PM7-Pad71)") (class "Default")
      (node (ref "U2") (pin "71") (pinfunction "PM7_71") (pintype "bidirectional+no_connect"))
    )
    (net (code "87") (name "unconnected-(U2B-PN0-Pad107)") (class "Default")
      (node (ref "U2") (pin "107") (pinfunction "PN0_107") (pintype "bidirectional+no_connect"))
    )
    (net (code "88") (name "unconnected-(U2B-PN1-Pad108)") (class "Default")
      (node (ref "U2") (pin "108") (pinfunction "PN1_108") (pintype "bidirectional+no_connect"))
    )
    (net (code "89") (name "unconnected-(U2B-PN2-Pad109)") (class "Default")
      (node (ref "U2") (pin "109") (pinfunction "PN2_109") (pintype "bidirectional+no_connect"))
    )
    (net (code "90") (name "unconnected-(U2B-PN3-Pad110)") (class "Default")
      (node (ref "U2") (pin "110") (pinfunction "PN3_110") (pintype "bidirectional+no_connect"))
    )
    (net (code "91") (name "unconnected-(U2B-PN4-Pad111)") (class "Default")
      (node (ref "U2") (pin "111") (pinfunction "PN4_111") (pintype "bidirectional+no_connect"))
    )
    (net (code "92") (name "unconnected-(U2B-PN5-Pad112)") (class "Default")
      (node (ref "U2") (pin "112") (pinfunction "PN5_112") (pintype "bidirectional+no_connect"))
    )
    (net (code "93") (name "unconnected-(U2B-PP0-Pad118)") (class "Default")
      (node (ref "U2") (pin "118") (pinfunction "PP0_118") (pintype "bidirectional+no_connect"))
    )
    (net (code "94") (name "unconnected-(U2B-PP1-Pad119)") (class "Default")
      (node (ref "U2") (pin "119") (pinfunction "PP1_119") (pintype "bidirectional+no_connect"))
    )
    (net (code "95") (name "unconnected-(U2B-PP2-Pad103)") (class "Default")
      (node (ref "U2") (pin "103") (pinfunction "PP2_103") (pintype "bidirectional+no_connect"))
    )
    (net (code "96") (name "unconnected-(U2B-PP3-Pad104)") (class "Default")
      (node (ref "U2") (pin "104") (pinfunction "PP3_104") (pintype "bidirectional+no_connect"))
    )
    (net (code "97") (name "unconnected-(U2B-PP4-Pad105)") (class "Default")
      (node (ref "U2") (pin "105") (pinfunction "PP4_105") (pintype "bidirectional+no_connect"))
    )
    (net (code "98") (name "unconnected-(U2B-PP5-Pad106)") (class "Default")
      (node (ref "U2") (pin "106") (pinfunction "PP5_106") (pintype "bidirectional+no_connect"))
    )
    (net (code "99") (name "unconnected-(U2B-PQ0-Pad5)") (class "Default")
      (node (ref "U2") (pin "5") (pinfunction "PQ0_5") (pintype "bidirectional+no_connect"))
    )
    (net (code "100") (name "unconnected-(U2B-PQ1-Pad6)") (class "Default")
      (node (ref "U2") (pin "6") (pinfunction "PQ1_6") (pintype "bidirectional+no_connect"))
    )
    (net (code "101") (name "unconnected-(U2B-PQ2-Pad11)") (class "Default")
      (node (ref "U2") (pin "11") (pinfunction "PQ2_11") (pintype "bidirectional+no_connect"))
    )
    (net (code "102") (name "unconnected-(U2B-PQ3-Pad27)") (class "Default")
      (node (ref "U2") (pin "27") (pinfunction "PQ3_27") (pintype "bidirectional+no_connect"))
    )
    (net (code "103") (name "unconnected-(U2B-PQ4-Pad102)") (class "Default")
      (node (ref "U2") (pin "102") (pinfunction "PQ4_102") (pintype "bidirectional+no_connect"))
    )
    (net (code "104") (name "unconnected-(U2C-EN0RXIN-Pad53)") (class "Default")
      (node (ref "U2") (pin "53") (pinfunction "EN0RXIN_53") (pintype "bidirectional+no_connect"))
    )
    (net (code "105") (name "unconnected-(U2C-EN0RXIP-Pad54)") (class "Default")
      (node (ref "U2") (pin "54") (pinfunction "EN0RXIP_54") (pintype "bidirectional+no_connect"))
    )
    (net (code "106") (name "unconnected-(U2C-EN0TXON-Pad56)") (class "Default")
      (node (ref "U2") (pin "56") (pinfunction "EN0TXON_56") (pintype "bidirectional+no_connect"))
    )
    (net (code "107") (name "unconnected-(U2C-EN0TXOP-Pad57)") (class "Default")
      (node (ref "U2") (pin "57") (pinfunction "EN0TXOP_57") (pintype "bidirectional+no_connect"))
    )
    (net (code "108") (name "unconnected-(U2C-HIB-Pad65)") (class "Default")
      (node (ref "U2") (pin "65") (pinfunction "HIB_65") (pintype "output+no_connect"))
    )
    (net (code "109") (name "unconnected-(U2C-XOSC1-Pad67)") (class "Default")
      (node (ref "U2") (pin "67") (pinfunction "XOSC1_67") (pintype "output+no_connect"))
    )
  )
)
